# Eth-Crystal.net
KiCad netlist of a schematic drawn in Altium Designer
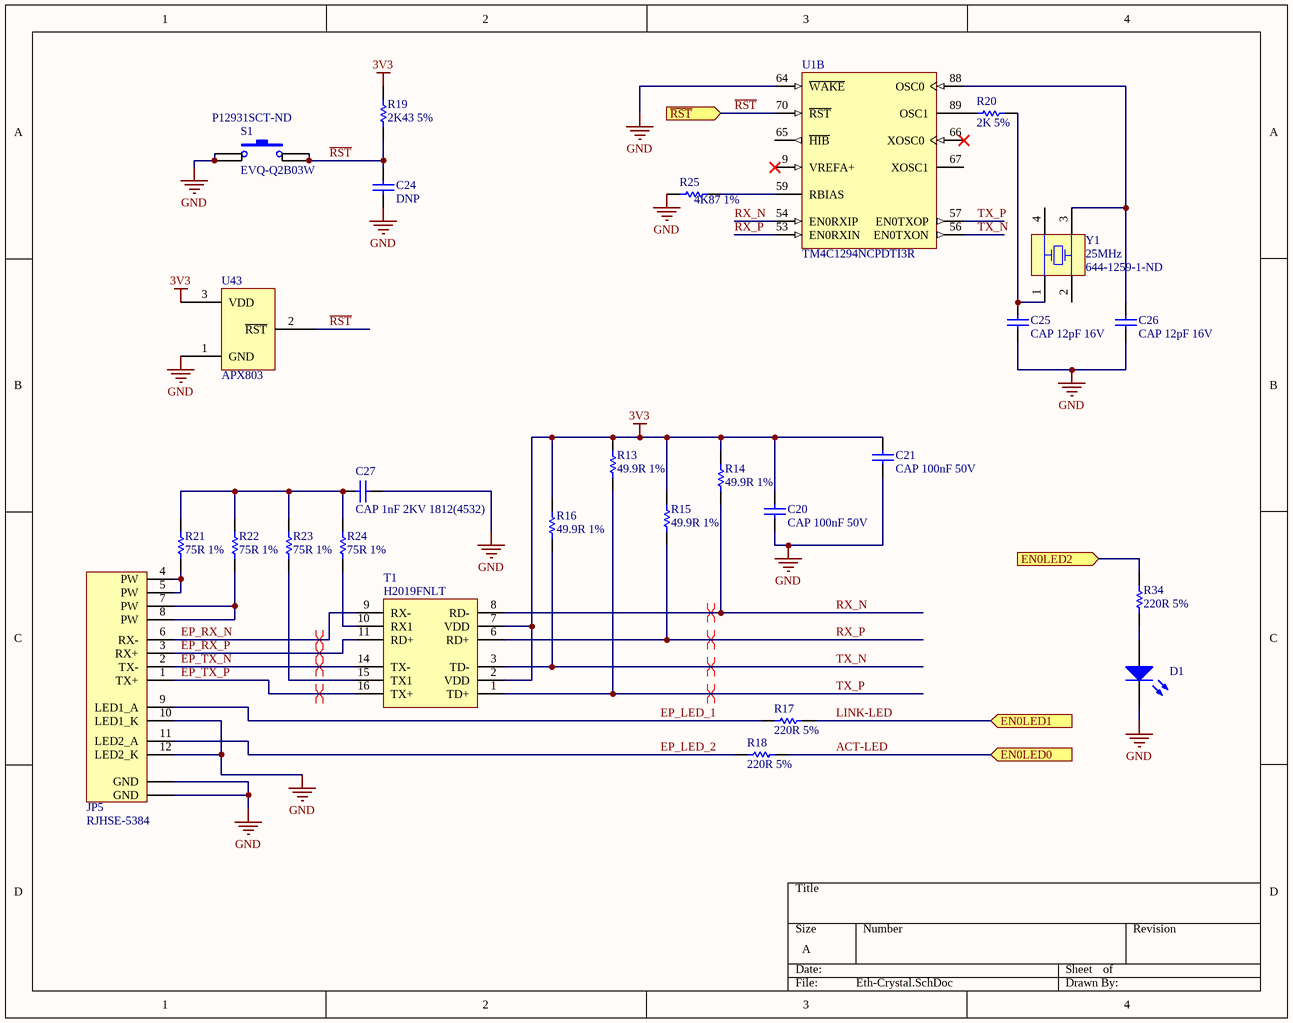
[diagram p0: Eth-Crystal.SchDoc]

(export (version "E")
  (design (tool "Eeschema 10.0.6"))
  (components
    (comp (ref "C20")
      (value "CAP 100nF 50V")
      (footprint "CAPC0603(1608)100_M")
      (description "CAP 100nF 50V Â±0.1pF 0603 (1608 Metric) Thickness 1mm SMD")
      (fields (field (name "TOLERANCE") "Â±0.1pF"))
      (libsource (lib "Altium Content Vault") (part "CMP-1035-00010-1"))
    )
    (comp (ref "C21")
      (value "CAP 100nF 50V")
      (footprint "CAPC0603(1608)100_M")
      (description "CAP 100nF 50V Â±0.1pF 0603 (1608 Metric) Thickness 1mm SMD")
      (fields (field (name "TOLERANCE") "Â±0.1pF"))
      (libsource (lib "Altium Content Vault") (part "CMP-1035-00010-1"))
    )
    (comp (ref "C24")
      (value "DNP")
      (footprint "0603")
      (description "100nF")
      (fields (field (name "PUBLISHER") "Altium Limited"))
      (libsource (lib "snarc+") (part "Cap_100pF"))
    )
    (comp (ref "C25")
      (value "CAP 12pF 16V")
      (footprint "CAPC0603(1608)100_L")
      (description "CAP 12pF 16V Â±0.25pF 0603 (1608 Metric) Thickness 1mm SMD")
      (fields (field (name "TOLERANCE") "Â±0.25pF"))
      (libsource (lib "Altium Content Vault") (part "CAP"))
    )
    (comp (ref "C26")
      (value "CAP 12pF 16V")
      (footprint "CAPC0603(1608)100_L")
      (description "CAP 12pF 16V Â±0.25pF 0603 (1608 Metric) Thickness 1mm SMD")
      (fields (field (name "TOLERANCE") "Â±0.25pF"))
      (libsource (lib "Altium Content Vault") (part "CAP"))
    )
    (comp (ref "C27")
      (value "CAP 1nF 2KV 1812(4532)")
      (footprint "CAPC1812(4532)230_N")
      (description "CAP 1nF 2KV Â±10% 1812 (4532 Metric) Thickness 2.3mm SMD")
      (fields (field (name "TOLERANCE") "Â±10%"))
      (libsource (lib "Altium Content Vault") (part "CAP"))
    )
    (comp (ref "D1")
      (value "LED")
      (footprint "LED-0603")
      (description "Typical RED, GREEN, YELLOW, AMBER GaAs LED")
      (fields (field (name "PUBLISHER") "Altium Limited"))
      (libsource (lib "HSBNE-Vend") (part "LED"))
    )
    (comp (ref "JP5")
      (value "RJHSE-5384")
      (footprint "RJHSE-5484")
      (description "Ethernet Socket RJ45 With Leds")
      (libsource (lib "snarc+") (part "Ethernet Socket"))
    )
    (comp (ref "R13")
      (value "49.9R 1%")
      (footprint "RESC0603(1608)_M")
      (description "49.9R 0.1W 1% 0603 (1608 Metric)  SMD")
      (fields (field (name "TOLERANCE") "5 %") (field (name "POWER") "0.1 W"))
      (libsource (lib "Altium Content Vault") (part "CMP-1012-00042-1"))
    )
    (comp (ref "R14")
      (value "49.9R 1%")
      (footprint "RESC0603(1608)_M")
      (description "49.9R 0.1W 1% 0603 (1608 Metric)  SMD")
      (fields (field (name "TOLERANCE") "5 %") (field (name "POWER") "0.1 W"))
      (libsource (lib "Altium Content Vault") (part "CMP-1012-00042-1"))
    )
    (comp (ref "R15")
      (value "49.9R 1%")
      (footprint "RESC0603(1608)_M")
      (description "49.9R 0.1W 1% 0603 (1608 Metric)  SMD")
      (fields (field (name "TOLERANCE") "5 %") (field (name "POWER") "0.1 W"))
      (libsource (lib "Altium Content Vault") (part "CMP-1012-00042-1"))
    )
    (comp (ref "R16")
      (value "49.9R 1%")
      (footprint "RESC0603(1608)_M")
      (description "49.9R 0.1W 1% 0603 (1608 Metric)  SMD")
      (fields (field (name "TOLERANCE") "5 %") (field (name "POWER") "0.1 W"))
      (libsource (lib "Altium Content Vault") (part "CMP-1012-00042-1"))
    )
    (comp (ref "R17")
      (value "220R 5%")
      (footprint "RESC0603(1608)_M")
      (description "220R 0.1W 5% 0603 (1608 Metric)  SMD")
      (fields (field (name "POWER") "0.1 W") (field (name "TOLERANCE") "5 %"))
      (libsource (lib "Altium Content Vault") (part "CMP-1012-00058-1"))
    )
    (comp (ref "R18")
      (value "220R 5%")
      (footprint "RESC0603(1608)_M")
      (description "220R 0.1W 5% 0603 (1608 Metric)  SMD")
      (fields (field (name "POWER") "0.1 W") (field (name "TOLERANCE") "5 %"))
      (libsource (lib "Altium Content Vault") (part "CMP-1012-00058-1"))
    )
    (comp (ref "R19")
      (value "2K43 5%")
      (footprint "RESC0603(1608)_M")
      (description "2K43 0.1W 5% 0603 (1608 Metric)  SMD")
      (fields (field (name "TOLERANCE") "5 %") (field (name "POWER") "0.1 W"))
      (libsource (lib "Altium Content Vault") (part "CMP-1012-00083-1"))
    )
    (comp (ref "R20")
      (value "2K 5%")
      (footprint "RESC0603(1608)_N")
      (description "2K 0.1W 5% 0603 (1608 Metric)  SMD")
      (fields (field (name "TOLERANCE") "5 %") (field (name "POWER") "0.1 W"))
      (libsource (lib "Altium Content Vault") (part "RES"))
    )
    (comp (ref "R21")
      (value "75R 1%")
      (footprint "RESC0603(1608)_N")
      (description "75R 0.1W 1% 0603 (1608 Metric)  SMD")
      (fields (field (name "TOLERANCE") "5 %") (field (name "POWER") "0.1 W"))
      (libsource (lib "Altium Content Vault") (part "CMP-1012-00047-1"))
    )
    (comp (ref "R22")
      (value "75R 1%")
      (footprint "RESC0603(1608)_N")
      (description "75R 0.1W 1% 0603 (1608 Metric)  SMD")
      (fields (field (name "TOLERANCE") "5 %") (field (name "POWER") "0.1 W"))
      (libsource (lib "Altium Content Vault") (part "CMP-1012-00047-1"))
    )
    (comp (ref "R23")
      (value "75R 1%")
      (footprint "RESC0603(1608)_N")
      (description "75R 0.1W 1% 0603 (1608 Metric)  SMD")
      (fields (field (name "TOLERANCE") "5 %") (field (name "POWER") "0.1 W"))
      (libsource (lib "Altium Content Vault") (part "CMP-1012-00047-1"))
    )
    (comp (ref "R24")
      (value "75R 1%")
      (footprint "RESC0603(1608)_N")
      (description "75R 0.1W 1% 0603 (1608 Metric)  SMD")
      (fields (field (name "TOLERANCE") "5 %") (field (name "POWER") "0.1 W"))
      (libsource (lib "Altium Content Vault") (part "CMP-1012-00047-1"))
    )
    (comp (ref "R25")
      (value "4K87 1%")
      (footprint "RESC0603(1608)_M")
      (description "4K87 0.1W 1% 0603 (1608 Metric)  SMD")
      (fields (field (name "TOLERANCE") "5 %") (field (name "POWER") "0.1 W"))
      (libsource (lib "Altium Content Vault") (part "CMP-1012-00090-1"))
    )
    (comp (ref "R34")
      (value "220R 5%")
      (footprint "RESC0603(1608)_M")
      (description "220R 0.1W 5% 0603 (1608 Metric)  SMD")
      (fields (field (name "POWER") "0.1 W") (field (name "TOLERANCE") "5 %"))
      (libsource (lib "Altium Content Vault") (part "CMP-1012-00058-1"))
    )
    (comp (ref "S1")
      (value "EVQ-Q2B03W")
      (footprint "TACTILE_SWITCH_SMD")
      (description "Switch")
      (fields
        (field (name "SUPPLIER PART NUMBER 1") "P12931SCT-ND")
        (field (name "PUBLISHER") "Altium Limited")
      )
      (libsource (lib "snarc+") (part "SW-PB"))
    )
    (comp (ref "T1")
      (value "H2019FNLT")
      (footprint "HXXXX")
      (description "Power over Ethernet Magnetic Module")
      (fields (field (name "PUBLISHER") "Altium Limited"))
      (libsource (lib "snarc+3") (part "Magnetics"))
    )
    (comp (ref "U1")
      (value "TM4C1294NCPDTI3R")
      (footprint "TI-PDT128_M")
      (fields (field (name "MANUFACTURER") "Texas Instruments"))
      (libsource (lib "Altium Inc") (part "TI-TM4C1294NCPDT-128"))
    )
    (comp (ref "U43")
      (value "APX803")
      (footprint "SOT-23 - ESD")
      (description "IC MPU RESET CIRC 3.08V SOT23R-3")
      (libsource (lib "HSBNE-Vend") (part "APX803"))
    )
    (comp (ref "Y1")
      (value "25MHz")
      (footprint "Crystal 3.2x2.5")
      (description "Surface Mount Quartz Crystal")
      (fields
        (field (name "SUPPLIER PART NUMBER 1") "644-1259-1-ND")
        (field (name "PUBLISHER") "Altium Limited")
      )
      (libsource (lib "HSBNE-Vend") (part "Crystal_25MHz"))
    )
  )
  (nets
    (net (code "1") (name "/ACT-LED") (class "Default")
      (node (ref "R18") (pin "2") (pinfunction "2_2") (pintype "passive"))
    )
    (net (code "2") (name "/EN0LED2") (class "Default")
      (node (ref "R34") (pin "2") (pinfunction "2_2") (pintype "passive"))
    )
    (net (code "3") (name "/EP_LED_1") (class "Default")
      (node (ref "JP5") (pin "9") (pinfunction "LED1_A_9") (pintype "passive"))
      (node (ref "R17") (pin "1") (pinfunction "1_1") (pintype "passive"))
    )
    (net (code "4") (name "/EP_LED_2") (class "Default")
      (node (ref "JP5") (pin "11") (pinfunction "LED2_A_11") (pintype "passive"))
      (node (ref "R18") (pin "1") (pinfunction "1_1") (pintype "passive"))
    )
    (net (code "5") (name "/EP_RX_N") (class "Default")
      (node (ref "JP5") (pin "6") (pinfunction "RX-_6") (pintype "passive"))
      (node (ref "T1") (pin "9") (pinfunction "RX-_9") (pintype "passive"))
    )
    (net (code "6") (name "/EP_RX_P") (class "Default")
      (node (ref "JP5") (pin "3") (pinfunction "RX+_3") (pintype "passive"))
      (node (ref "T1") (pin "11") (pinfunction "RD+_11") (pintype "passive"))
    )
    (net (code "7") (name "/EP_TX_N") (class "Default")
      (node (ref "JP5") (pin "2") (pinfunction "TX-_2") (pintype "passive"))
      (node (ref "T1") (pin "14") (pinfunction "TX-_14") (pintype "passive"))
    )
    (net (code "8") (name "/EP_TX_P") (class "Default")
      (node (ref "JP5") (pin "1") (pinfunction "TX+_1") (pintype "passive"))
      (node (ref "T1") (pin "16") (pinfunction "TX+_16") (pintype "passive"))
    )
    (net (code "9") (name "/LINK-LED") (class "Default")
      (node (ref "R17") (pin "2") (pinfunction "2_2") (pintype "passive"))
    )
    (net (code "10") (name "/RX_N") (class "Default")
      (node (ref "R14") (pin "1") (pinfunction "1_1") (pintype "passive"))
      (node (ref "T1") (pin "8") (pinfunction "RD-_8") (pintype "passive"))
      (node (ref "U1") (pin "54") (pinfunction "EN0RXIP_54") (pintype "input"))
    )
    (net (code "11") (name "/RX_P") (class "Default")
      (node (ref "R15") (pin "1") (pinfunction "1_1") (pintype "passive"))
      (node (ref "T1") (pin "6") (pinfunction "RD+_6") (pintype "passive"))
      (node (ref "U1") (pin "53") (pinfunction "EN0RXIN_53") (pintype "input"))
    )
    (net (code "12") (name "/TX_N") (class "Default")
      (node (ref "R16") (pin "1") (pinfunction "1_1") (pintype "passive"))
      (node (ref "T1") (pin "3") (pinfunction "TD-_3") (pintype "passive"))
      (node (ref "U1") (pin "56") (pinfunction "EN0TXON_56") (pintype "output"))
    )
    (net (code "13") (name "/TX_P") (class "Default")
      (node (ref "R13") (pin "1") (pinfunction "1_1") (pintype "passive"))
      (node (ref "T1") (pin "1") (pinfunction "TD+_1") (pintype "passive"))
      (node (ref "U1") (pin "57") (pinfunction "EN0TXOP_57") (pintype "output"))
    )
    (net (code "14") (name "/~{RST}") (class "Default")
      (node (ref "C24") (pin "2") (pinfunction "2_2") (pintype "passive"))
      (node (ref "R19") (pin "1") (pinfunction "1_1") (pintype "passive"))
      (node (ref "S1") (pin "3") (pinfunction "3_3") (pintype "passive"))
      (node (ref "S1") (pin "4") (pinfunction "4_4") (pintype "passive"))
      (node (ref "U1") (pin "70") (pinfunction "~{RST}_70") (pintype "input"))
      (node (ref "U43") (pin "2") (pinfunction "~{RST}_2") (pintype "passive"))
    )
    (net (code "15") (name "3V3") (class "Default")
      (node (ref "C20") (pin "2") (pinfunction "2_2") (pintype "passive"))
      (node (ref "C21") (pin "2") (pinfunction "2_2") (pintype "passive"))
      (node (ref "R13") (pin "2") (pinfunction "2_2") (pintype "passive"))
      (node (ref "R14") (pin "2") (pinfunction "2_2") (pintype "passive"))
      (node (ref "R15") (pin "2") (pinfunction "2_2") (pintype "passive"))
      (node (ref "R16") (pin "2") (pinfunction "2_2") (pintype "passive"))
      (node (ref "R19") (pin "2") (pinfunction "2_2") (pintype "passive"))
      (node (ref "T1") (pin "2") (pinfunction "VDD_2") (pintype "passive"))
      (node (ref "T1") (pin "7") (pinfunction "VDD_7") (pintype "passive"))
      (node (ref "U43") (pin "3") (pinfunction "VDD_3") (pintype "passive"))
    )
    (net (code "16") (name "GND") (class "Default")
      (node (ref "C20") (pin "1") (pinfunction "1_1") (pintype "passive"))
      (node (ref "C21") (pin "1") (pinfunction "1_1") (pintype "passive"))
      (node (ref "C24") (pin "1") (pinfunction "1_1") (pintype "passive"))
      (node (ref "C25") (pin "1") (pinfunction "1_1") (pintype "passive"))
      (node (ref "C26") (pin "1") (pinfunction "1_1") (pintype "passive"))
      (node (ref "C27") (pin "2") (pinfunction "2_2") (pintype "passive"))
      (node (ref "D1") (pin "2") (pinfunction "K_2") (pintype "passive"))
      (node (ref "JP5") (pin "10") (pinfunction "LED1_K_10") (pintype "passive"))
      (node (ref "JP5") (pin "12") (pinfunction "LED2_K_12") (pintype "passive"))
      (node (ref "JP5") (pin "GND1") (pinfunction "GND_GND1") (pintype "passive"))
      (node (ref "JP5") (pin "GND2") (pinfunction "GND_GND2") (pintype "passive"))
      (node (ref "R25") (pin "1") (pinfunction "1_1") (pintype "passive"))
      (node (ref "S1") (pin "1") (pinfunction "1_1") (pintype "passive"))
      (node (ref "S1") (pin "2") (pinfunction "2_2") (pintype "passive"))
      (node (ref "U1") (pin "64") (pinfunction "~{WAKE}_64") (pintype "input"))
      (node (ref "U43") (pin "1") (pinfunction "GND_1") (pintype "passive"))
    )
    (net (code "17") (name "Net-(C25-Pad2)") (class "Default")
      (node (ref "C25") (pin "2") (pinfunction "2_2") (pintype "passive"))
      (node (ref "R20") (pin "2") (pinfunction "2_2") (pintype "passive"))
      (node (ref "Y1") (pin "1") (pinfunction "OSC1_1") (pintype "passive"))
    )
    (net (code "18") (name "Net-(C27-Pad1)") (class "Default")
      (node (ref "C27") (pin "1") (pinfunction "1_1") (pintype "passive"))
      (node (ref "R21") (pin "2") (pinfunction "2_2") (pintype "passive"))
      (node (ref "R22") (pin "2") (pinfunction "2_2") (pintype "passive"))
      (node (ref "R23") (pin "2") (pinfunction "2_2") (pintype "passive"))
      (node (ref "R24") (pin "2") (pinfunction "2_2") (pintype "passive"))
    )
    (net (code "19") (name "Net-(D1-A)") (class "Default")
      (node (ref "D1") (pin "1") (pinfunction "A_1") (pintype "passive"))
      (node (ref "R34") (pin "1") (pinfunction "1_1") (pintype "passive"))
    )
    (net (code "20") (name "Net-(JP5-PW-Pad4)") (class "Default")
      (node (ref "JP5") (pin "4") (pinfunction "PW_4") (pintype "passive"))
      (node (ref "JP5") (pin "5") (pinfunction "PW_5") (pintype "passive"))
      (node (ref "R21") (pin "1") (pinfunction "1_1") (pintype "passive"))
    )
    (net (code "21") (name "Net-(JP5-PW-Pad7)") (class "Default")
      (node (ref "JP5") (pin "7") (pinfunction "PW_7") (pintype "passive"))
      (node (ref "JP5") (pin "8") (pinfunction "PW_8") (pintype "passive"))
      (node (ref "R22") (pin "1") (pinfunction "1_1") (pintype "passive"))
    )
    (net (code "22") (name "Net-(T1-RX1)") (class "Default")
      (node (ref "R24") (pin "1") (pinfunction "1_1") (pintype "passive"))
      (node (ref "T1") (pin "10") (pinfunction "RX1_10") (pintype "passive"))
    )
    (net (code "23") (name "Net-(T1-TX1)") (class "Default")
      (node (ref "R23") (pin "1") (pinfunction "1_1") (pintype "passive"))
      (node (ref "T1") (pin "15") (pinfunction "TX1_15") (pintype "passive"))
    )
    (net (code "24") (name "Net-(U1B-OSC0)") (class "Default")
      (node (ref "C26") (pin "2") (pinfunction "2_2") (pintype "passive"))
      (node (ref "U1") (pin "88") (pinfunction "OSC0_88") (pintype "input"))
      (node (ref "Y1") (pin "3") (pinfunction "OSC2_3") (pintype "passive"))
    )
    (net (code "25") (name "Net-(U1B-OSC1)") (class "Default")
      (node (ref "R20") (pin "1") (pinfunction "1_1") (pintype "passive"))
      (node (ref "U1") (pin "89") (pinfunction "OSC1_89") (pintype "passive"))
    )
    (net (code "26") (name "Net-(U1B-RBIAS)") (class "Default")
      (node (ref "R25") (pin "2") (pinfunction "2_2") (pintype "passive"))
      (node (ref "U1") (pin "59") (pinfunction "RBIAS_59") (pintype "passive"))
    )
    (net (code "27") (name "unconnected-(U1B-VREFA+-Pad9)") (class "Default")
      (node (ref "U1") (pin "9") (pinfunction "VREFA+_9") (pintype "input+no_connect"))
    )
    (net (code "28") (name "unconnected-(U1B-XOSC0-Pad66)") (class "Default")
      (node (ref "U1") (pin "66") (pinfunction "XOSC0_66") (pintype "input+no_connect"))
    )
    (net (code "29") (name "unconnected-(U1B-XOSC1-Pad67)") (class "Default")
      (node (ref "U1") (pin "67") (pinfunction "XOSC1_67") (pintype "passive"))
    )
    (net (code "30") (name "unconnected-(U1B-~{HIB}-Pad65)") (class "Default")
      (node (ref "U1") (pin "65") (pinfunction "~{HIB}_65") (pintype "output"))
    )
    (net (code "31") (name "unconnected-(Y1-OSC1-Pad4)") (class "Default")
      (node (ref "Y1") (pin "4") (pinfunction "OSC1_4") (pintype "passive"))
    )
    (net (code "32") (name "unconnected-(Y1-OSC2-Pad2)") (class "Default")
      (node (ref "Y1") (pin "2") (pinfunction "OSC2_2") (pintype "passive"))
    )
  )
)
